# NPC.net
KiCad netlist of a schematic drawn in EAGLE
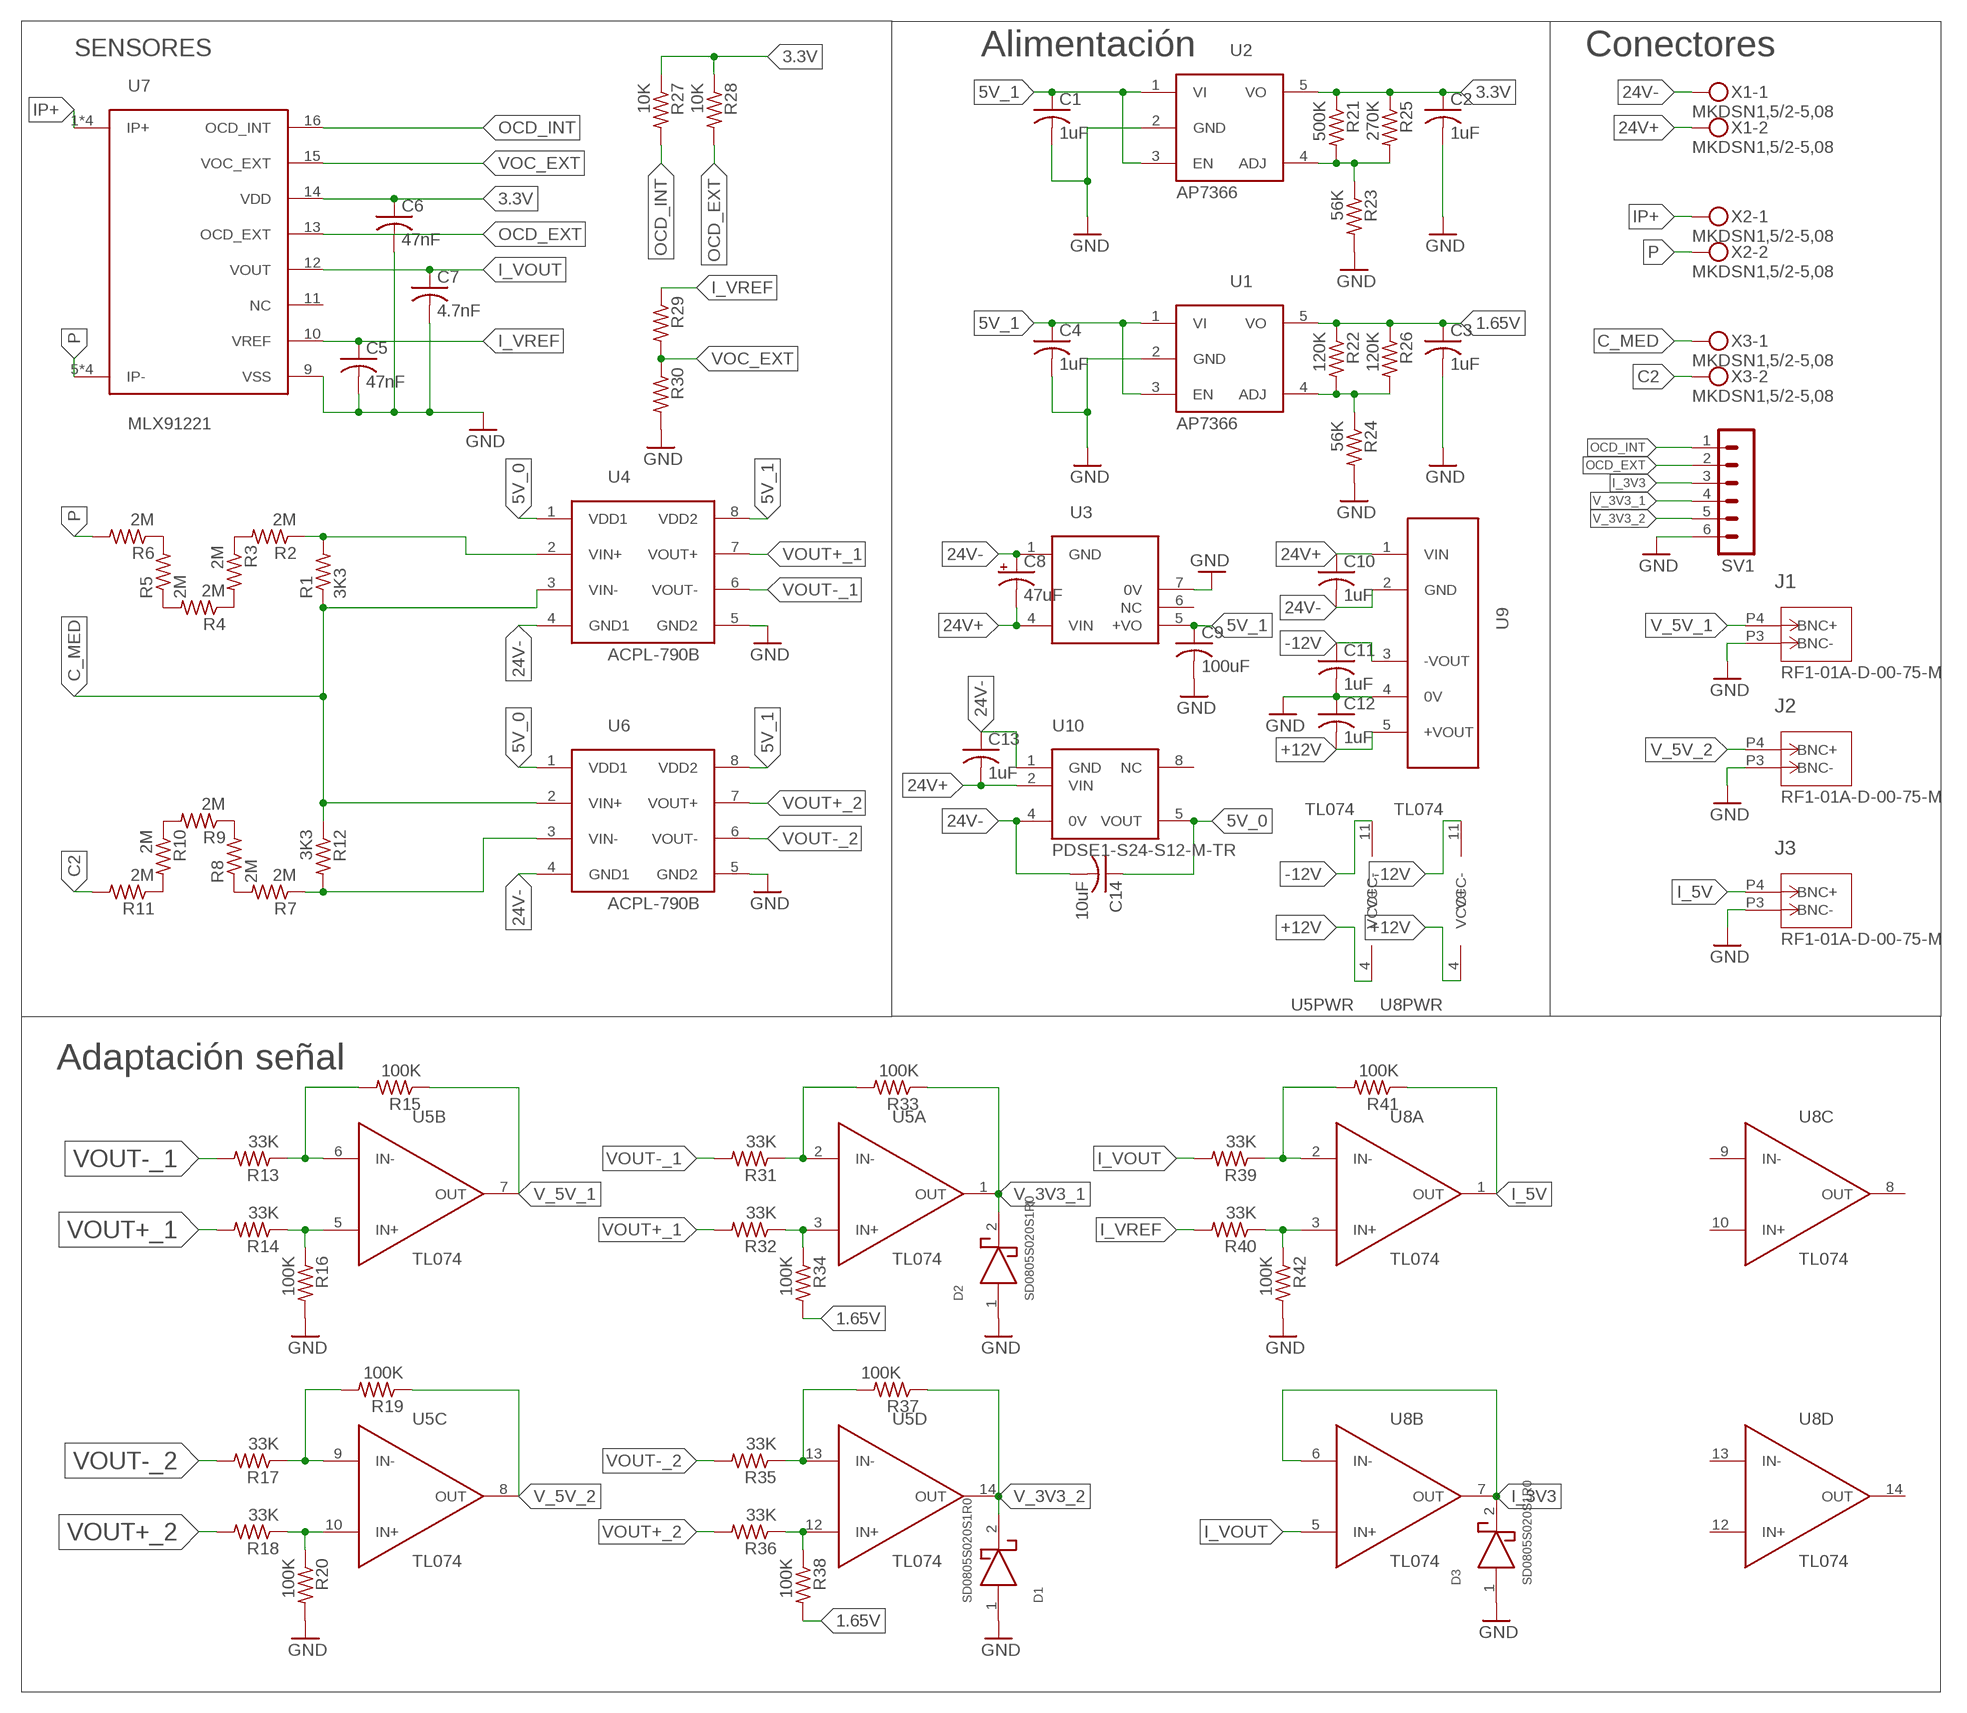
[diagram p0: schematic, sheet 1]

(export (version "E")
  (design (tool "Eeschema 10.0.6"))
  (components
    (comp (ref "C1")
      (value "1uF")
      (footprint "eagle-import:C0805")
      (fields (field (name "PARTNO") "GRM219R61H105KA73D"))
      (libsource (lib "eagle-import") (part "C-USC0805"))
    )
    (comp (ref "C2")
      (value "1uF")
      (footprint "eagle-import:C0805")
      (fields (field (name "PARTNO") "GRM219R61H105KA73D"))
      (libsource (lib "eagle-import") (part "C-USC0805"))
    )
    (comp (ref "C3")
      (value "1uF")
      (footprint "eagle-import:C0805")
      (fields (field (name "PARTNO") "GRM219R61H105KA73D"))
      (libsource (lib "eagle-import") (part "C-USC0805"))
    )
    (comp (ref "C4")
      (value "1uF")
      (footprint "eagle-import:C0805")
      (fields (field (name "PARTNO") "GRM219R61H105KA73D"))
      (libsource (lib "eagle-import") (part "C-USC0805"))
    )
    (comp (ref "C5")
      (value "47nF")
      (footprint "eagle-import:C0805")
      (fields (field (name "PARTNO") "CC0805JRX7R7BB473"))
      (libsource (lib "eagle-import") (part "C-USC0805"))
    )
    (comp (ref "C6")
      (value "47nF")
      (footprint "eagle-import:C0805")
      (fields (field (name "PARTNO") "CC0805JRX7R7BB473"))
      (libsource (lib "eagle-import") (part "C-USC0805"))
    )
    (comp (ref "C7")
      (value "4.7nF")
      (footprint "eagle-import:C0805")
      (fields (field (name "PARTNO") "0805ZC472KAT2A"))
      (libsource (lib "eagle-import") (part "C-USC0805"))
    )
    (comp (ref "C8")
      (value "47uF")
      (footprint "eagle-import:175TMP-0808")
      (fields (field (name "PARTNO") "HHXC630ARA470MHA0G"))
      (libsource (lib "eagle-import") (part "CPOL-US175TMP-0808"))
    )
    (comp (ref "C9")
      (value "100uF")
      (footprint "eagle-import:C0805")
      (fields (field (name "PARTNO") "GRM21BR60J107ME15L"))
      (libsource (lib "eagle-import") (part "C-USC0805"))
    )
    (comp (ref "C10")
      (value "1uF")
      (footprint "eagle-import:C0805")
      (fields (field (name "PARTNO") "GRM219R61H105KA73D"))
      (libsource (lib "eagle-import") (part "C-USC0805"))
    )
    (comp (ref "C11")
      (value "1uF")
      (footprint "eagle-import:C0805")
      (fields (field (name "PARTNO") "GRM219R61H105KA73D"))
      (libsource (lib "eagle-import") (part "C-USC0805"))
    )
    (comp (ref "C12")
      (value "1uF")
      (footprint "eagle-import:C0805")
      (fields (field (name "PARTNO") "GRM219R61H105KA73D"))
      (libsource (lib "eagle-import") (part "C-USC0805"))
    )
    (comp (ref "C13")
      (value "1uF")
      (footprint "eagle-import:C0805")
      (fields (field (name "PARTNO") "GRM219R61H105KA73D"))
      (libsource (lib "eagle-import") (part "C-USC0805"))
    )
    (comp (ref "C14")
      (value "10uF")
      (footprint "eagle-import:C0805")
      (fields (field (name "PARTNO") "GRM21BC71C106KE11L"))
      (libsource (lib "eagle-import") (part "C-USC0805"))
    )
    (comp (ref "D1")
      (value "SD0805S020S1R0")
      (footprint "eagle-import:0805")
      (libsource (lib "eagle-import") (part "SD0805S020S1R0"))
    )
    (comp (ref "D2")
      (value "SD0805S020S1R0")
      (footprint "eagle-import:0805")
      (libsource (lib "eagle-import") (part "SD0805S020S1R0"))
    )
    (comp (ref "D3")
      (value "SD0805S020S1R0")
      (footprint "eagle-import:0805")
      (libsource (lib "eagle-import") (part "SD0805S020S1R0"))
    )
    (comp (ref "J1")
      (value "RF1-01A-D-00-75-M")
      (footprint "eagle-import:BNC")
      (libsource (lib "eagle-import") (part "RF1-01A-D-00-75-M"))
    )
    (comp (ref "J2")
      (value "RF1-01A-D-00-75-M")
      (footprint "eagle-import:BNC")
      (libsource (lib "eagle-import") (part "RF1-01A-D-00-75-M"))
    )
    (comp (ref "J3")
      (value "RF1-01A-D-00-75-M")
      (footprint "eagle-import:BNC")
      (libsource (lib "eagle-import") (part "RF1-01A-D-00-75-M"))
    )
    (comp (ref "R1")
      (value "3K3")
      (footprint "eagle-import:R1206")
      (fields (field (name "PARTNO") "ERJ-S08F3301V"))
      (libsource (lib "eagle-import") (part "R-US_R1206"))
    )
    (comp (ref "R2")
      (value "2M")
      (footprint "eagle-import:R1206")
      (fields (field (name "PARTNO") "RCV12062M00FKEA"))
      (libsource (lib "eagle-import") (part "R-US_R1206"))
    )
    (comp (ref "R3")
      (value "2M")
      (footprint "eagle-import:R1206")
      (fields (field (name "PARTNO") "RCV12062M00FKEA"))
      (libsource (lib "eagle-import") (part "R-US_R1206"))
    )
    (comp (ref "R4")
      (value "2M")
      (footprint "eagle-import:R1206")
      (fields (field (name "PARTNO") "RCV12062M00FKEA"))
      (libsource (lib "eagle-import") (part "R-US_R1206"))
    )
    (comp (ref "R5")
      (value "2M")
      (footprint "eagle-import:R1206")
      (fields (field (name "PARTNO") "RCV12062M00FKEA"))
      (libsource (lib "eagle-import") (part "R-US_R1206"))
    )
    (comp (ref "R6")
      (value "2M")
      (footprint "eagle-import:R1206")
      (fields (field (name "PARTNO") "RCV12062M00FKEA"))
      (libsource (lib "eagle-import") (part "R-US_R1206"))
    )
    (comp (ref "R7")
      (value "2M")
      (footprint "eagle-import:R1206")
      (fields (field (name "PARTNO") "RCV12062M00FKEA"))
      (libsource (lib "eagle-import") (part "R-US_R1206"))
    )
    (comp (ref "R8")
      (value "2M")
      (footprint "eagle-import:R1206")
      (fields (field (name "PARTNO") "RCV12062M00FKEA"))
      (libsource (lib "eagle-import") (part "R-US_R1206"))
    )
    (comp (ref "R9")
      (value "2M")
      (footprint "eagle-import:R1206")
      (fields (field (name "PARTNO") "RCV12062M00FKEA"))
      (libsource (lib "eagle-import") (part "R-US_R1206"))
    )
    (comp (ref "R10")
      (value "2M")
      (footprint "eagle-import:R1206")
      (fields (field (name "PARTNO") "RCV12062M00FKEA"))
      (libsource (lib "eagle-import") (part "R-US_R1206"))
    )
    (comp (ref "R11")
      (value "2M")
      (footprint "eagle-import:R1206")
      (fields (field (name "PARTNO") "RCV12062M00FKEA"))
      (libsource (lib "eagle-import") (part "R-US_R1206"))
    )
    (comp (ref "R12")
      (value "3K3")
      (footprint "eagle-import:R1206")
      (fields (field (name "PARTNO") "ERJ-S08F3301V"))
      (libsource (lib "eagle-import") (part "R-US_R1206"))
    )
    (comp (ref "R13")
      (value "33K")
      (footprint "eagle-import:M0805")
      (fields (field (name "PARTNO") "CR0805-FX-3302ELF"))
      (libsource (lib "eagle-import") (part "R-US_M0805"))
    )
    (comp (ref "R14")
      (value "33K")
      (footprint "eagle-import:M0805")
      (fields (field (name "PARTNO") "CR0805-FX-3302ELF"))
      (libsource (lib "eagle-import") (part "R-US_M0805"))
    )
    (comp (ref "R15")
      (value "100K")
      (footprint "eagle-import:M0805")
      (fields (field (name "PARTNO") "CR0805-FX-1003ELF"))
      (libsource (lib "eagle-import") (part "R-US_M0805"))
    )
    (comp (ref "R16")
      (value "100K")
      (footprint "eagle-import:M0805")
      (fields (field (name "PARTNO") "CR0805-FX-1003ELF"))
      (libsource (lib "eagle-import") (part "R-US_M0805"))
    )
    (comp (ref "R17")
      (value "33K")
      (footprint "eagle-import:M0805")
      (fields (field (name "PARTNO") "CR0805-FX-3302ELF"))
      (libsource (lib "eagle-import") (part "R-US_M0805"))
    )
    (comp (ref "R18")
      (value "33K")
      (footprint "eagle-import:M0805")
      (fields (field (name "PARTNO") "CR0805-FX-3302ELF"))
      (libsource (lib "eagle-import") (part "R-US_M0805"))
    )
    (comp (ref "R19")
      (value "100K")
      (footprint "eagle-import:M0805")
      (fields (field (name "PARTNO") "CR0805-FX-1003ELF"))
      (libsource (lib "eagle-import") (part "R-US_M0805"))
    )
    (comp (ref "R20")
      (value "100K")
      (footprint "eagle-import:M0805")
      (fields (field (name "PARTNO") "CR0805-FX-1003ELF"))
      (libsource (lib "eagle-import") (part "R-US_M0805"))
    )
    (comp (ref "R21")
      (value "500K")
      (footprint "eagle-import:M0805")
      (fields (field (name "PARTNO") "CR0805-FX-4993ELF"))
      (libsource (lib "eagle-import") (part "R-US_M0805"))
    )
    (comp (ref "R22")
      (value "120K")
      (footprint "eagle-import:M0805")
      (fields (field (name "PARTNO") "CRCW0805120KFKEAC"))
      (libsource (lib "eagle-import") (part "R-US_M0805"))
    )
    (comp (ref "R23")
      (value "56K")
      (footprint "eagle-import:M0805")
      (fields (field (name "PARTNO") "CR0805-FX-5602ELF"))
      (libsource (lib "eagle-import") (part "R-US_M0805"))
    )
    (comp (ref "R24")
      (value "56K")
      (footprint "eagle-import:M0805")
      (fields (field (name "PARTNO") "CR0805-FX-5602ELF"))
      (libsource (lib "eagle-import") (part "R-US_M0805"))
    )
    (comp (ref "R25")
      (value "270K")
      (footprint "eagle-import:M0805")
      (fields (field (name "PARTNO") "CRCW0805270KFKEAC"))
      (libsource (lib "eagle-import") (part "R-US_M0805"))
    )
    (comp (ref "R26")
      (value "120K")
      (footprint "eagle-import:M0805")
      (fields (field (name "PARTNO") "CRCW0805120KFKEAC"))
      (libsource (lib "eagle-import") (part "R-US_M0805"))
    )
    (comp (ref "R27")
      (value "10K")
      (footprint "eagle-import:M0805")
      (fields (field (name "PARTNO") "CR0805-FX-1002ELF"))
      (libsource (lib "eagle-import") (part "R-US_M0805"))
    )
    (comp (ref "R28")
      (value "10K")
      (footprint "eagle-import:M0805")
      (fields (field (name "PARTNO") "CR0805-FX-1002ELF"))
      (libsource (lib "eagle-import") (part "R-US_M0805"))
    )
    (comp (ref "R29")
      (value "R-US_M0805")
      (footprint "eagle-import:M0805")
      (libsource (lib "eagle-import") (part "R-US_M0805"))
    )
    (comp (ref "R30")
      (value "R-US_M0805")
      (footprint "eagle-import:M0805")
      (libsource (lib "eagle-import") (part "R-US_M0805"))
    )
    (comp (ref "R31")
      (value "33K")
      (footprint "eagle-import:M0805")
      (fields (field (name "PARTNO") "CR0805-FX-3302ELF"))
      (libsource (lib "eagle-import") (part "R-US_M0805"))
    )
    (comp (ref "R32")
      (value "33K")
      (footprint "eagle-import:M0805")
      (fields (field (name "PARTNO") "CR0805-FX-3302ELF"))
      (libsource (lib "eagle-import") (part "R-US_M0805"))
    )
    (comp (ref "R33")
      (value "100K")
      (footprint "eagle-import:M0805")
      (fields (field (name "PARTNO") "CR0805-FX-1003ELF"))
      (libsource (lib "eagle-import") (part "R-US_M0805"))
    )
    (comp (ref "R34")
      (value "100K")
      (footprint "eagle-import:M0805")
      (fields (field (name "PARTNO") "CR0805-FX-1003ELF"))
      (libsource (lib "eagle-import") (part "R-US_M0805"))
    )
    (comp (ref "R35")
      (value "33K")
      (footprint "eagle-import:M0805")
      (fields (field (name "PARTNO") "CR0805-FX-3302ELF"))
      (libsource (lib "eagle-import") (part "R-US_M0805"))
    )
    (comp (ref "R36")
      (value "33K")
      (footprint "eagle-import:M0805")
      (fields (field (name "PARTNO") "CR0805-FX-3302ELF"))
      (libsource (lib "eagle-import") (part "R-US_M0805"))
    )
    (comp (ref "R37")
      (value "100K")
      (footprint "eagle-import:M0805")
      (fields (field (name "PARTNO") "CR0805-FX-1003ELF"))
      (libsource (lib "eagle-import") (part "R-US_M0805"))
    )
    (comp (ref "R38")
      (value "100K")
      (footprint "eagle-import:M0805")
      (fields (field (name "PARTNO") "CR0805-FX-1003ELF"))
      (libsource (lib "eagle-import") (part "R-US_M0805"))
    )
    (comp (ref "R39")
      (value "33K")
      (footprint "eagle-import:M0805")
      (fields (field (name "PARTNO") "CR0805-FX-3302ELF"))
      (libsource (lib "eagle-import") (part "R-US_M0805"))
    )
    (comp (ref "R40")
      (value "33K")
      (footprint "eagle-import:M0805")
      (fields (field (name "PARTNO") "CR0805-FX-3302ELF"))
      (libsource (lib "eagle-import") (part "R-US_M0805"))
    )
    (comp (ref "R41")
      (value "100K")
      (footprint "eagle-import:M0805")
      (fields (field (name "PARTNO") "CR0805-FX-1003ELF"))
      (libsource (lib "eagle-import") (part "R-US_M0805"))
    )
    (comp (ref "R42")
      (value "100K")
      (footprint "eagle-import:M0805")
      (fields (field (name "PARTNO") "CR0805-FX-1003ELF"))
      (libsource (lib "eagle-import") (part "R-US_M0805"))
    )
    (comp (ref "SV1")
      (value "MA06-1")
      (footprint "eagle-import:MA06-1")
      (fields (field (name "PARTNO") "M20-9750342"))
      (libsource (lib "eagle-import") (part "MA06-1"))
    )
    (comp (ref "U1")
      (value "AP7366")
      (footprint "eagle-import:SOT25")
      (fields (field (name "PARTNO") "AP7366-W5-7"))
      (libsource (lib "eagle-import") (part "AP7366"))
    )
    (comp (ref "U2")
      (value "AP7366")
      (footprint "eagle-import:SOT25")
      (fields (field (name "PARTNO") "AP7366-W5-7"))
      (libsource (lib "eagle-import") (part "AP7366"))
    )
    (comp (ref "U3")
      (value "PQP3-D24-S5-M-TR")
      (footprint "eagle-import:DIP-5")
      (libsource (lib "eagle-import") (part "PQP3-D24-S5-M-TR"))
    )
    (comp (ref "U4")
      (value "ACPL-790B")
      (footprint "eagle-import:DIP-8")
      (fields (field (name "PARTNO") "ACPL-790B-300E"))
      (libsource (lib "eagle-import") (part "ACPL-790B"))
    )
    (comp (ref "U5")
      (value "TL074")
      (footprint "eagle-import:SO-14")
      (fields (field (name "PARTNO") "TL074CDT"))
      (libsource (lib "eagle-import") (part "TL074"))
    )
    (comp (ref "U6")
      (value "ACPL-790B")
      (footprint "eagle-import:DIP-8")
      (fields (field (name "PARTNO") "ACPL-790B-300E"))
      (libsource (lib "eagle-import") (part "ACPL-790B"))
    )
    (comp (ref "U7")
      (value "MLX91221")
      (footprint "eagle-import:SOIC-16W")
      (fields (field (name "PARTNO") "MLX91221KDF-ABF-025-RE"))
      (libsource (lib "eagle-import") (part "MLX91221"))
    )
    (comp (ref "U8")
      (value "TL074")
      (footprint "eagle-import:SO-14")
      (fields (field (name "PARTNO") "TL074CDT"))
      (libsource (lib "eagle-import") (part "TL074"))
    )
    (comp (ref "U9")
      (value "PEM2-S24-D12-S")
      (footprint "eagle-import:SIP-5")
      (libsource (lib "eagle-import") (part "PEM2-S24-D12-S"))
    )
    (comp (ref "U10")
      (value "PDSE1-S24-S12-M-TR")
      (footprint "eagle-import:PDSE1-S24-S12-M-TR")
      (fields (field (name "PARTNO") "PQP3-D24-S5-M-TR"))
      (libsource (lib "eagle-import") (part "PDSE1-S24-S12-M-TR"))
    )
    (comp (ref "X1")
      (value "MKDSN1,5/2-5,08")
      (footprint "eagle-import:MKDSN1,5_2-5,08")
      (fields (field (name "PARTNO") "1797952"))
      (libsource (lib "eagle-import") (part "MKDSN1,5/2-5,08"))
    )
    (comp (ref "X2")
      (value "MKDSN1,5/2-5,08")
      (footprint "eagle-import:MKDSN1,5_2-5,08")
      (fields (field (name "PARTNO") "1797952"))
      (libsource (lib "eagle-import") (part "MKDSN1,5/2-5,08"))
    )
    (comp (ref "X3")
      (value "MKDSN1,5/2-5,08")
      (footprint "eagle-import:MKDSN1,5_2-5,08")
      (fields (field (name "PARTNO") "1797952"))
      (libsource (lib "eagle-import") (part "MKDSN1,5/2-5,08"))
    )
  )
  (nets
    (net (code "1") (name "+12V") (class "Default")
      (node (ref "C12") (pin "2") (pinfunction "2_2") (pintype "passive"))
      (node (ref "U5") (pin "4") (pinfunction "VCC+_4") (pintype "power_in"))
      (node (ref "U8") (pin "4") (pinfunction "VCC+_4") (pintype "power_in"))
      (node (ref "U9") (pin "5") (pinfunction "+VOUT_5") (pintype "passive"))
    )
    (net (code "2") (name "-12V") (class "Default")
      (node (ref "C11") (pin "1") (pinfunction "1_1") (pintype "passive"))
      (node (ref "U5") (pin "11") (pinfunction "VCC-_11") (pintype "power_in"))
      (node (ref "U8") (pin "11") (pinfunction "VCC-_11") (pintype "power_in"))
      (node (ref "U9") (pin "3") (pinfunction "-VOUT_3") (pintype "passive"))
    )
    (net (code "3") (name "1.65V") (class "Default")
      (node (ref "C3") (pin "1") (pinfunction "1_1") (pintype "passive"))
      (node (ref "R22") (pin "1") (pinfunction "1_1") (pintype "passive"))
      (node (ref "R26") (pin "1") (pinfunction "1_1") (pintype "passive"))
      (node (ref "R34") (pin "2") (pinfunction "2_2") (pintype "passive"))
      (node (ref "R38") (pin "2") (pinfunction "2_2") (pintype "passive"))
      (node (ref "U1") (pin "5") (pinfunction "VO_5") (pintype "power_in"))
    )
    (net (code "4") (name "3.3V") (class "Default")
      (node (ref "C2") (pin "1") (pinfunction "1_1") (pintype "passive"))
      (node (ref "C6") (pin "1") (pinfunction "1_1") (pintype "passive"))
      (node (ref "R21") (pin "1") (pinfunction "1_1") (pintype "passive"))
      (node (ref "R25") (pin "1") (pinfunction "1_1") (pintype "passive"))
      (node (ref "R27") (pin "1") (pinfunction "1_1") (pintype "passive"))
      (node (ref "R28") (pin "1") (pinfunction "1_1") (pintype "passive"))
      (node (ref "U2") (pin "5") (pinfunction "VO_5") (pintype "power_in"))
      (node (ref "U7") (pin "14") (pinfunction "VDD_14") (pintype "power_in"))
    )
    (net (code "5") (name "5V_0") (class "Default")
      (node (ref "C14") (pin "1") (pinfunction "1_1") (pintype "passive"))
      (node (ref "U10") (pin "5") (pinfunction "VOUT_5") (pintype "passive"))
      (node (ref "U4") (pin "1") (pinfunction "VDD1_1") (pintype "power_in"))
      (node (ref "U6") (pin "1") (pinfunction "VDD1_1") (pintype "power_in"))
    )
    (net (code "6") (name "5V_1") (class "Default")
      (node (ref "C1") (pin "1") (pinfunction "1_1") (pintype "passive"))
      (node (ref "C4") (pin "1") (pinfunction "1_1") (pintype "passive"))
      (node (ref "C9") (pin "1") (pinfunction "1_1") (pintype "passive"))
      (node (ref "U1") (pin "1") (pinfunction "VI_1") (pintype "power_in"))
      (node (ref "U1") (pin "3") (pinfunction "EN_3") (pintype "passive"))
      (node (ref "U2") (pin "1") (pinfunction "VI_1") (pintype "power_in"))
      (node (ref "U2") (pin "3") (pinfunction "EN_3") (pintype "passive"))
      (node (ref "U3") (pin "5") (pinfunction "+VO_5") (pintype "passive"))
      (node (ref "U4") (pin "8") (pinfunction "VDD2_8") (pintype "power_in"))
      (node (ref "U6") (pin "8") (pinfunction "VDD2_8") (pintype "power_in"))
    )
    (net (code "7") (name "24V+") (class "Default")
      (node (ref "C10") (pin "1") (pinfunction "1_1") (pintype "passive"))
      (node (ref "C13") (pin "2") (pinfunction "2_2") (pintype "passive"))
      (node (ref "C8") (pin "-") (pinfunction "-_-") (pintype "passive"))
      (node (ref "U10") (pin "2") (pinfunction "VIN_2") (pintype "passive"))
      (node (ref "U3") (pin "4") (pinfunction "VIN_4") (pintype "passive"))
      (node (ref "U9") (pin "1") (pinfunction "VIN_1") (pintype "passive"))
      (node (ref "X1") (pin "2") (pinfunction "KL_2") (pintype "passive"))
    )
    (net (code "8") (name "24V-") (class "Default")
      (node (ref "C10") (pin "2") (pinfunction "2_2") (pintype "passive"))
      (node (ref "C13") (pin "1") (pinfunction "1_1") (pintype "passive"))
      (node (ref "C14") (pin "2") (pinfunction "2_2") (pintype "passive"))
      (node (ref "C8") (pin "+") (pinfunction "+_+") (pintype "passive"))
      (node (ref "U10") (pin "1") (pinfunction "GND_1") (pintype "passive"))
      (node (ref "U10") (pin "4") (pinfunction "0V_4") (pintype "passive"))
      (node (ref "U3") (pin "1") (pinfunction "GND_1") (pintype "passive"))
      (node (ref "U4") (pin "4") (pinfunction "GND1_4") (pintype "power_in"))
      (node (ref "U6") (pin "4") (pinfunction "GND1_4") (pintype "power_in"))
      (node (ref "U9") (pin "2") (pinfunction "GND_2") (pintype "passive"))
      (node (ref "X1") (pin "1") (pinfunction "KL_1") (pintype "passive"))
    )
    (net (code "9") (name "C2") (class "Default")
      (node (ref "R11") (pin "2") (pinfunction "2_2") (pintype "passive"))
      (node (ref "X3") (pin "2") (pinfunction "KL_2") (pintype "passive"))
    )
    (net (code "10") (name "C_MED") (class "Default")
      (node (ref "R1") (pin "1") (pinfunction "1_1") (pintype "passive"))
      (node (ref "R12") (pin "1") (pinfunction "1_1") (pintype "passive"))
      (node (ref "U4") (pin "3") (pinfunction "VIN-_3") (pintype "input"))
      (node (ref "U6") (pin "2") (pinfunction "VIN+_2") (pintype "input"))
      (node (ref "X3") (pin "1") (pinfunction "KL_1") (pintype "passive"))
    )
    (net (code "11") (name "GND") (class "Default")
      (node (ref "C1") (pin "2") (pinfunction "2_2") (pintype "passive"))
      (node (ref "C11") (pin "2") (pinfunction "2_2") (pintype "passive"))
      (node (ref "C12") (pin "1") (pinfunction "1_1") (pintype "passive"))
      (node (ref "C2") (pin "2") (pinfunction "2_2") (pintype "passive"))
      (node (ref "C3") (pin "2") (pinfunction "2_2") (pintype "passive"))
      (node (ref "C4") (pin "2") (pinfunction "2_2") (pintype "passive"))
      (node (ref "C5") (pin "2") (pinfunction "2_2") (pintype "passive"))
      (node (ref "C6") (pin "2") (pinfunction "2_2") (pintype "passive"))
      (node (ref "C7") (pin "2") (pinfunction "2_2") (pintype "passive"))
      (node (ref "C9") (pin "2") (pinfunction "2_2") (pintype "passive"))
      (node (ref "D1") (pin "1") (pinfunction "D+_1") (pintype "passive"))
      (node (ref "D2") (pin "1") (pinfunction "D+_1") (pintype "passive"))
      (node (ref "D3") (pin "1") (pinfunction "D+_1") (pintype "passive"))
      (node (ref "J1") (pin "P3") (pinfunction "BNC-_P3") (pintype "passive"))
      (node (ref "J2") (pin "P3") (pinfunction "BNC-_P3") (pintype "passive"))
      (node (ref "J3") (pin "P3") (pinfunction "BNC-_P3") (pintype "passive"))
      (node (ref "R16") (pin "2") (pinfunction "2_2") (pintype "passive"))
      (node (ref "R20") (pin "2") (pinfunction "2_2") (pintype "passive"))
      (node (ref "R23") (pin "2") (pinfunction "2_2") (pintype "passive"))
      (node (ref "R24") (pin "2") (pinfunction "2_2") (pintype "passive"))
      (node (ref "R30") (pin "2") (pinfunction "2_2") (pintype "passive"))
      (node (ref "R42") (pin "2") (pinfunction "2_2") (pintype "passive"))
      (node (ref "SV1") (pin "6") (pinfunction "6_6") (pintype "passive"))
      (node (ref "U1") (pin "2") (pinfunction "GND_2") (pintype "power_in"))
      (node (ref "U2") (pin "2") (pinfunction "GND_2") (pintype "power_in"))
      (node (ref "U3") (pin "7") (pinfunction "0V_7") (pintype "passive"))
      (node (ref "U4") (pin "5") (pinfunction "GND2_5") (pintype "power_in"))
      (node (ref "U6") (pin "5") (pinfunction "GND2_5") (pintype "power_in"))
      (node (ref "U7") (pin "9") (pinfunction "VSS_9") (pintype "power_in"))
      (node (ref "U9") (pin "4") (pinfunction "0V_4") (pintype "passive"))
    )
    (net (code "12") (name "IP+") (class "Default")
      (node (ref "U7") (pin "1") (pinfunction "IP+_1") (pintype "passive"))
      (node (ref "U7") (pin "2") (pinfunction "IP+_2") (pintype "passive"))
      (node (ref "U7") (pin "3") (pinfunction "IP+_3") (pintype "passive"))
      (node (ref "U7") (pin "4") (pinfunction "IP+_4") (pintype "passive"))
      (node (ref "X2") (pin "1") (pinfunction "KL_1") (pintype "passive"))
    )
    (net (code "13") (name "I_3V3") (class "Default")
      (node (ref "D3") (pin "2") (pinfunction "D-_2") (pintype "bidirectional"))
      (node (ref "SV1") (pin "3") (pinfunction "3_3") (pintype "passive"))
      (node (ref "U8") (pin "6") (pinfunction "IN-_6") (pintype "passive"))
      (node (ref "U8") (pin "7") (pinfunction "OUT_7") (pintype "passive"))
    )
    (net (code "14") (name "I_5V") (class "Default")
      (node (ref "J3") (pin "P4") (pinfunction "BNC+_P4") (pintype "passive"))
      (node (ref "R41") (pin "1") (pinfunction "1_1") (pintype "passive"))
      (node (ref "U8") (pin "1") (pinfunction "OUT_1") (pintype "passive"))
    )
    (net (code "15") (name "I_VOUT") (class "Default")
      (node (ref "C7") (pin "1") (pinfunction "1_1") (pintype "passive"))
      (node (ref "R39") (pin "2") (pinfunction "2_2") (pintype "passive"))
      (node (ref "U7") (pin "12") (pinfunction "VOUT_12") (pintype "passive"))
      (node (ref "U8") (pin "5") (pinfunction "IN+_5") (pintype "passive"))
    )
    (net (code "16") (name "I_VREF") (class "Default")
      (node (ref "C5") (pin "1") (pinfunction "1_1") (pintype "passive"))
      (node (ref "R29") (pin "1") (pinfunction "1_1") (pintype "passive"))
      (node (ref "R40") (pin "2") (pinfunction "2_2") (pintype "passive"))
      (node (ref "U7") (pin "10") (pinfunction "VREF_10") (pintype "passive"))
    )
    (net (code "17") (name "Net-(R2-Pad2)") (class "Default")
      (node (ref "R2") (pin "2") (pinfunction "2_2") (pintype "passive"))
      (node (ref "R3") (pin "1") (pinfunction "1_1") (pintype "passive"))
    )
    (net (code "18") (name "Net-(R3-Pad2)") (class "Default")
      (node (ref "R3") (pin "2") (pinfunction "2_2") (pintype "passive"))
      (node (ref "R4") (pin "1") (pinfunction "1_1") (pintype "passive"))
    )
    (net (code "19") (name "Net-(R4-Pad2)") (class "Default")
      (node (ref "R4") (pin "2") (pinfunction "2_2") (pintype "passive"))
      (node (ref "R5") (pin "1") (pinfunction "1_1") (pintype "passive"))
    )
    (net (code "20") (name "Net-(R5-Pad2)") (class "Default")
      (node (ref "R5") (pin "2") (pinfunction "2_2") (pintype "passive"))
      (node (ref "R6") (pin "1") (pinfunction "1_1") (pintype "passive"))
    )
    (net (code "21") (name "Net-(R7-Pad2)") (class "Default")
      (node (ref "R7") (pin "2") (pinfunction "2_2") (pintype "passive"))
      (node (ref "R8") (pin "1") (pinfunction "1_1") (pintype "passive"))
    )
    (net (code "22") (name "Net-(R8-Pad2)") (class "Default")
      (node (ref "R8") (pin "2") (pinfunction "2_2") (pintype "passive"))
      (node (ref "R9") (pin "1") (pinfunction "1_1") (pintype "passive"))
    )
    (net (code "23") (name "Net-(R10-Pad1)") (class "Default")
      (node (ref "R10") (pin "1") (pinfunction "1_1") (pintype "passive"))
      (node (ref "R9") (pin "2") (pinfunction "2_2") (pintype "passive"))
    )
    (net (code "24") (name "Net-(R10-Pad2)") (class "Default")
      (node (ref "R10") (pin "2") (pinfunction "2_2") (pintype "passive"))
      (node (ref "R11") (pin "1") (pinfunction "1_1") (pintype "passive"))
    )
    (net (code "25") (name "Net-(U1-ADJ)") (class "Default")
      (node (ref "R22") (pin "2") (pinfunction "2_2") (pintype "passive"))
      (node (ref "R24") (pin "1") (pinfunction "1_1") (pintype "passive"))
      (node (ref "R26") (pin "2") (pinfunction "2_2") (pintype "passive"))
      (node (ref "U1") (pin "4") (pinfunction "ADJ_4") (pintype "passive"))
    )
    (net (code "26") (name "Net-(U2-ADJ)") (class "Default")
      (node (ref "R21") (pin "2") (pinfunction "2_2") (pintype "passive"))
      (node (ref "R23") (pin "1") (pinfunction "1_1") (pintype "passive"))
      (node (ref "R25") (pin "2") (pinfunction "2_2") (pintype "passive"))
      (node (ref "U2") (pin "4") (pinfunction "ADJ_4") (pintype "passive"))
    )
    (net (code "27") (name "Net-(U4-VIN+)") (class "Default")
      (node (ref "R1") (pin "2") (pinfunction "2_2") (pintype "passive"))
      (node (ref "R2") (pin "1") (pinfunction "1_1") (pintype "passive"))
      (node (ref "U4") (pin "2") (pinfunction "VIN+_2") (pintype "input"))
    )
    (net (code "28") (name "Net-(U5A-IN+)") (class "Default")
      (node (ref "R32") (pin "1") (pinfunction "1_1") (pintype "passive"))
      (node (ref "R34") (pin "1") (pinfunction "1_1") (pintype "passive"))
      (node (ref "U5") (pin "3") (pinfunction "IN+_3") (pintype "passive"))
    )
    (net (code "29") (name "Net-(U5A-IN-)") (class "Default")
      (node (ref "R31") (pin "1") (pinfunction "1_1") (pintype "passive"))
      (node (ref "R33") (pin "2") (pinfunction "2_2") (pintype "passive"))
      (node (ref "U5") (pin "2") (pinfunction "IN-_2") (pintype "passive"))
    )
    (net (code "30") (name "Net-(U5B-IN+)") (class "Default")
      (node (ref "R14") (pin "1") (pinfunction "1_1") (pintype "passive"))
      (node (ref "R16") (pin "1") (pinfunction "1_1") (pintype "passive"))
      (node (ref "U5") (pin "5") (pinfunction "IN+_5") (pintype "passive"))
    )
    (net (code "31") (name "Net-(U5B-IN-)") (class "Default")
      (node (ref "R13") (pin "1") (pinfunction "1_1") (pintype "passive"))
      (node (ref "R15") (pin "2") (pinfunction "2_2") (pintype "passive"))
      (node (ref "U5") (pin "6") (pinfunction "IN-_6") (pintype "passive"))
    )
    (net (code "32") (name "Net-(U5C-IN+)") (class "Default")
      (node (ref "R18") (pin "1") (pinfunction "1_1") (pintype "passive"))
      (node (ref "R20") (pin "1") (pinfunction "1_1") (pintype "passive"))
      (node (ref "U5") (pin "10") (pinfunction "IN+_10") (pintype "passive"))
    )
    (net (code "33") (name "Net-(U5C-IN-)") (class "Default")
      (node (ref "R17") (pin "1") (pinfunction "1_1") (pintype "passive"))
      (node (ref "R19") (pin "2") (pinfunction "2_2") (pintype "passive"))
      (node (ref "U5") (pin "9") (pinfunction "IN-_9") (pintype "passive"))
    )
    (net (code "34") (name "Net-(U5D-IN+)") (class "Default")
      (node (ref "R36") (pin "1") (pinfunction "1_1") (pintype "passive"))
      (node (ref "R38") (pin "1") (pinfunction "1_1") (pintype "passive"))
      (node (ref "U5") (pin "12") (pinfunction "IN+_12") (pintype "passive"))
    )
    (net (code "35") (name "Net-(U5D-IN-)") (class "Default")
      (node (ref "R35") (pin "1") (pinfunction "1_1") (pintype "passive"))
      (node (ref "R37") (pin "2") (pinfunction "2_2") (pintype "passive"))
      (node (ref "U5") (pin "13") (pinfunction "IN-_13") (pintype "passive"))
    )
    (net (code "36") (name "Net-(U6-VIN-)") (class "Default")
      (node (ref "R12") (pin "2") (pinfunction "2_2") (pintype "passive"))
      (node (ref "R7") (pin "1") (pinfunction "1_1") (pintype "passive"))
      (node (ref "U6") (pin "3") (pinfunction "VIN-_3") (pintype "input"))
    )
    (net (code "37") (name "Net-(U8A-IN+)") (class "Default")
      (node (ref "R40") (pin "1") (pinfunction "1_1") (pintype "passive"))
      (node (ref "R42") (pin "1") (pinfunction "1_1") (pintype "passive"))
      (node (ref "U8") (pin "3") (pinfunction "IN+_3") (pintype "passive"))
    )
    (net (code "38") (name "Net-(U8A-IN-)") (class "Default")
      (node (ref "R39") (pin "1") (pinfunction "1_1") (pintype "passive"))
      (node (ref "R41") (pin "2") (pinfunction "2_2") (pintype "passive"))
      (node (ref "U8") (pin "2") (pinfunction "IN-_2") (pintype "passive"))
    )
    (net (code "39") (name "OCD_EXT") (class "Default")
      (node (ref "R28") (pin "2") (pinfunction "2_2") (pintype "passive"))
      (node (ref "SV1") (pin "2") (pinfunction "2_2") (pintype "passive"))
      (node (ref "U7") (pin "13") (pinfunction "OCD_EXT_13") (pintype "passive"))
    )
    (net (code "40") (name "OCD_INT") (class "Default")
      (node (ref "R27") (pin "2") (pinfunction "2_2") (pintype "passive"))
      (node (ref "SV1") (pin "1") (pinfunction "1_1") (pintype "passive"))
      (node (ref "U7") (pin "16") (pinfunction "OCD_INT_16") (pintype "passive"))
    )
    (net (code "41") (name "P") (class "Default")
      (node (ref "R6") (pin "2") (pinfunction "2_2") (pintype "passive"))
      (node (ref "U7") (pin "5") (pinfunction "IP-_5") (pintype "passive"))
      (node (ref "U7") (pin "6") (pinfunction "IP-_6") (pintype "passive"))
      (node (ref "U7") (pin "7") (pinfunction "IP-_7") (pintype "passive"))
      (node (ref "U7") (pin "8") (pinfunction "IP-_8") (pintype "passive"))
      (node (ref "X2") (pin "2") (pinfunction "KL_2") (pintype "passive"))
    )
    (net (code "42") (name "VOC_EXT") (class "Default")
      (node (ref "R29") (pin "2") (pinfunction "2_2") (pintype "passive"))
      (node (ref "R30") (pin "1") (pinfunction "1_1") (pintype "passive"))
      (node (ref "U7") (pin "15") (pinfunction "VOC_EXT_15") (pintype "passive"))
    )
    (net (code "43") (name "VOUT+_1") (class "Default")
      (node (ref "R14") (pin "2") (pinfunction "2_2") (pintype "passive"))
      (node (ref "R32") (pin "2") (pinfunction "2_2") (pintype "passive"))
      (node (ref "U4") (pin "7") (pinfunction "VOUT+_7") (pintype "output"))
    )
    (net (code "44") (name "VOUT+_2") (class "Default")
      (node (ref "R18") (pin "2") (pinfunction "2_2") (pintype "passive"))
      (node (ref "R36") (pin "2") (pinfunction "2_2") (pintype "passive"))
      (node (ref "U6") (pin "7") (pinfunction "VOUT+_7") (pintype "output"))
    )
    (net (code "45") (name "VOUT-_1") (class "Default")
      (node (ref "R13") (pin "2") (pinfunction "2_2") (pintype "passive"))
      (node (ref "R31") (pin "2") (pinfunction "2_2") (pintype "passive"))
      (node (ref "U4") (pin "6") (pinfunction "VOUT-_6") (pintype "output"))
    )
    (net (code "46") (name "VOUT-_2") (class "Default")
      (node (ref "R17") (pin "2") (pinfunction "2_2") (pintype "passive"))
      (node (ref "R35") (pin "2") (pinfunction "2_2") (pintype "passive"))
      (node (ref "U6") (pin "6") (pinfunction "VOUT-_6") (pintype "output"))
    )
    (net (code "47") (name "V_3V3_1") (class "Default")
      (node (ref "D2") (pin "2") (pinfunction "D-_2") (pintype "bidirectional"))
      (node (ref "R33") (pin "1") (pinfunction "1_1") (pintype "passive"))
      (node (ref "SV1") (pin "4") (pinfunction "4_4") (pintype "passive"))
      (node (ref "U5") (pin "1") (pinfunction "OUT_1") (pintype "passive"))
    )
    (net (code "48") (name "V_3V3_2") (class "Default")
      (node (ref "D1") (pin "2") (pinfunction "D-_2") (pintype "bidirectional"))
      (node (ref "R37") (pin "1") (pinfunction "1_1") (pintype "passive"))
      (node (ref "SV1") (pin "5") (pinfunction "5_5") (pintype "passive"))
      (node (ref "U5") (pin "14") (pinfunction "OUT_14") (pintype "passive"))
    )
    (net (code "49") (name "V_5V_1") (class "Default")
      (node (ref "J1") (pin "P4") (pinfunction "BNC+_P4") (pintype "passive"))
      (node (ref "R15") (pin "1") (pinfunction "1_1") (pintype "passive"))
      (node (ref "U5") (pin "7") (pinfunction "OUT_7") (pintype "passive"))
    )
    (net (code "50") (name "V_5V_2") (class "Default")
      (node (ref "J2") (pin "P4") (pinfunction "BNC+_P4") (pintype "passive"))
      (node (ref "R19") (pin "1") (pinfunction "1_1") (pintype "passive"))
      (node (ref "U5") (pin "8") (pinfunction "OUT_8") (pintype "passive"))
    )
    (net (code "51") (name "unconnected-(U3-NC-Pad6)") (class "Default")
      (node (ref "U3") (pin "6") (pinfunction "NC_6") (pintype "no_connect"))
    )
    (net (code "52") (name "unconnected-(U7-NC-Pad11)") (class "Default")
      (node (ref "U7") (pin "11") (pinfunction "NC_11") (pintype "no_connect"))
    )
    (net (code "53") (name "unconnected-(U8C-IN+-Pad10)") (class "Default")
      (node (ref "U8") (pin "10") (pinfunction "IN+_10") (pintype "passive"))
    )
    (net (code "54") (name "unconnected-(U8C-IN--Pad9)") (class "Default")
      (node (ref "U8") (pin "9") (pinfunction "IN-_9") (pintype "passive"))
    )
    (net (code "55") (name "unconnected-(U8C-OUT-Pad8)") (class "Default")
      (node (ref "U8") (pin "8") (pinfunction "OUT_8") (pintype "passive"))
    )
    (net (code "56") (name "unconnected-(U8D-IN+-Pad12)") (class "Default")
      (node (ref "U8") (pin "12") (pinfunction "IN+_12") (pintype "passive"))
    )
    (net (code "57") (name "unconnected-(U8D-IN--Pad13)") (class "Default")
      (node (ref "U8") (pin "13") (pinfunction "IN-_13") (pintype "passive"))
    )
    (net (code "58") (name "unconnected-(U8D-OUT-Pad14)") (class "Default")
      (node (ref "U8") (pin "14") (pinfunction "OUT_14") (pintype "passive"))
    )
    (net (code "59") (name "unconnected-(U10-NC-Pad8)") (class "Default")
      (node (ref "U10") (pin "8") (pinfunction "NC_8") (pintype "no_connect"))
    )
  )
)
